# elka2_tubes.net
KiCad netlist of a schematic drawn in Altium Designer
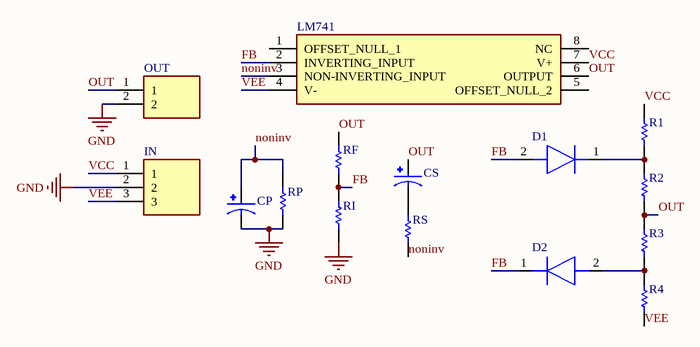
[diagram p0: elka2_tubes.SchDoc]

(export (version "E")
  (design (tool "Eeschema 10.0.6"))
  (components
    (comp (ref "CP")
      (value "elco_kecil")
      (footprint "elco_kecil")
      (description "CAP ALUM 10UF 20% 25V RADIAL")
      (fields (field (name "MF") "Panasonic") (field (name "MP") "EEA-GA1E100"))
      (libsource (lib "elco_kecil") (part "elco_kecil"))
    )
    (comp (ref "CS")
      (value "elco_kecil")
      (footprint "elco_kecil")
      (description "CAP ALUM 10UF 20% 25V RADIAL")
      (fields (field (name "MF") "Panasonic") (field (name "MP") "EEA-GA1E100"))
      (libsource (lib "elco_kecil") (part "elco_kecil"))
    )
    (comp (ref "D1")
      (value "1N4007-E3_73")
      (footprint "SamacSys:DIOAD1405W86L465D235")
      (description "Diode")
      (fields
        (field (name "MANUFACTURER_PART_NUMBER") "1N4007-E3/73")
        (field (name "MOUSER PART NUMBER") "625-1N4007-E3/73")
      )
      (libsource (lib "*") (part "1N4007-E3_73"))
    )
    (comp (ref "D2")
      (value "1N4007-E3_73")
      (footprint "SamacSys:DIOAD1405W86L465D235")
      (description "Diode")
      (fields
        (field (name "MANUFACTURER_PART_NUMBER") "1N4007-E3/73")
        (field (name "MOUSER PART NUMBER") "625-1N4007-E3/73")
      )
      (libsource (lib "*") (part "1N4007-E3_73"))
    )
    (comp (ref "IN")
      (value "KF301-3P")
      (footprint "SamacSys:KF3013P")
      (description "Connector")
      (libsource (lib "SamacSys") (part "KF301-3P"))
    )
    (comp (ref "LM741")
      (value "LM741CN_NOPB-936607701")
      (footprint "SamacSys:DIP794W53P254L959H508Q8N")
      (description "Integrated Circuit")
      (fields (field (name "MANUFACTURER_PART_NUMBER") "LM741CN/NOPB-936607701"))
      (libsource (lib "*") (part "LM741CN_NOPB-936607701"))
    )
    (comp (ref "OUT")
      (value "KF301-2P")
      (footprint "SamacSys:KF3012P")
      (description "Connector")
      (libsource (lib "SamacSys") (part "KF301-2P"))
    )
    (comp (ref "R1")
      (value "Resistor 0.25W")
      (footprint "Resistor 0.25W")
      (libsource (lib "GAPlib_DEVICES") (part "Resistor 0.25W"))
    )
    (comp (ref "R2")
      (value "Resistor 0.25W")
      (footprint "Resistor 0.25W")
      (libsource (lib "GAPlib_DEVICES") (part "Resistor 0.25W"))
    )
    (comp (ref "R3")
      (value "Resistor 0.25W")
      (footprint "Resistor 0.25W")
      (libsource (lib "GAPlib_DEVICES") (part "Resistor 0.25W"))
    )
    (comp (ref "R4")
      (value "Resistor 0.25W")
      (footprint "Resistor 0.25W")
      (libsource (lib "GAPlib_DEVICES") (part "Resistor 0.25W"))
    )
    (comp (ref "RF")
      (value "Resistor 0.25W")
      (footprint "Resistor 0.25W")
      (libsource (lib "GAPlib_DEVICES") (part "Resistor 0.25W"))
    )
    (comp (ref "RI")
      (value "Resistor 0.25W")
      (footprint "Resistor 0.25W")
      (libsource (lib "GAPlib_DEVICES") (part "Resistor 0.25W"))
    )
    (comp (ref "RP")
      (value "Resistor 0.25W")
      (footprint "Resistor 0.25W")
      (libsource (lib "GAPlib_DEVICES") (part "Resistor 0.25W"))
    )
    (comp (ref "RS")
      (value "Resistor 0.25W")
      (footprint "Resistor 0.25W")
      (libsource (lib "GAPlib_DEVICES") (part "Resistor 0.25W"))
    )
  )
  (nets
    (net (code "1") (name "/FB") (class "Default")
      (node (ref "D1") (pin "2") (pinfunction "A_2") (pintype "passive"))
      (node (ref "D2") (pin "1") (pinfunction "K_1") (pintype "passive"))
      (node (ref "LM741") (pin "2") (pinfunction "INVERTING_INPUT_2") (pintype "passive"))
      (node (ref "RF") (pin "1") (pinfunction "1_1") (pintype "passive"))
      (node (ref "RI") (pin "2") (pinfunction "2_2") (pintype "passive"))
    )
    (net (code "2") (name "/OUT") (class "Default")
      (node (ref "CS") (pin "P") (pinfunction "P_P") (pintype "passive"))
      (node (ref "LM741") (pin "6") (pinfunction "OUTPUT_6") (pintype "passive"))
      (node (ref "OUT") (pin "1") (pinfunction "1_1") (pintype "passive"))
      (node (ref "R2") (pin "1") (pinfunction "1_1") (pintype "passive"))
      (node (ref "R3") (pin "2") (pinfunction "2_2") (pintype "passive"))
      (node (ref "RF") (pin "2") (pinfunction "2_2") (pintype "passive"))
    )
    (net (code "3") (name "/VCC") (class "Default")
      (node (ref "IN") (pin "1") (pinfunction "1_1") (pintype "passive"))
      (node (ref "LM741") (pin "7") (pinfunction "V+_7") (pintype "passive"))
      (node (ref "R1") (pin "2") (pinfunction "2_2") (pintype "passive"))
    )
    (net (code "4") (name "/VEE") (class "Default")
      (node (ref "IN") (pin "3") (pinfunction "3_3") (pintype "passive"))
      (node (ref "LM741") (pin "4") (pinfunction "V-_4") (pintype "passive"))
      (node (ref "R4") (pin "1") (pinfunction "1_1") (pintype "passive"))
    )
    (net (code "5") (name "/noninv") (class "Default")
      (node (ref "CP") (pin "P") (pinfunction "P_P") (pintype "passive"))
      (node (ref "LM741") (pin "3") (pinfunction "NON-INVERTING_INPUT_3") (pintype "passive"))
      (node (ref "RP") (pin "2") (pinfunction "2_2") (pintype "passive"))
      (node (ref "RS") (pin "1") (pinfunction "1_1") (pintype "passive"))
    )
    (net (code "6") (name "GND") (class "Default")
      (node (ref "CP") (pin "N") (pinfunction "N_N") (pintype "passive"))
      (node (ref "IN") (pin "2") (pinfunction "2_2") (pintype "passive"))
      (node (ref "OUT") (pin "2") (pinfunction "2_2") (pintype "passive"))
      (node (ref "RI") (pin "1") (pinfunction "1_1") (pintype "passive"))
      (node (ref "RP") (pin "1") (pinfunction "1_1") (pintype "passive"))
    )
    (net (code "7") (name "Net-(CS-PadN)") (class "Default")
      (node (ref "CS") (pin "N") (pinfunction "N_N") (pintype "passive"))
      (node (ref "RS") (pin "2") (pinfunction "2_2") (pintype "passive"))
    )
    (net (code "8") (name "Net-(D1-K)") (class "Default")
      (node (ref "D1") (pin "1") (pinfunction "K_1") (pintype "passive"))
      (node (ref "R1") (pin "1") (pinfunction "1_1") (pintype "passive"))
      (node (ref "R2") (pin "2") (pinfunction "2_2") (pintype "passive"))
    )
    (net (code "9") (name "Net-(D2-A)") (class "Default")
      (node (ref "D2") (pin "2") (pinfunction "A_2") (pintype "passive"))
      (node (ref "R3") (pin "1") (pinfunction "1_1") (pintype "passive"))
      (node (ref "R4") (pin "2") (pinfunction "2_2") (pintype "passive"))
    )
    (net (code "10") (name "unconnected-(LM741-NC-Pad8)") (class "Default")
      (node (ref "LM741") (pin "8") (pinfunction "NC_8") (pintype "passive"))
    )
    (net (code "11") (name "unconnected-(LM741-OFFSET_NULL_1-Pad1)") (class "Default")
      (node (ref "LM741") (pin "1") (pinfunction "OFFSET_NULL_1_1") (pintype "passive"))
    )
    (net (code "12") (name "unconnected-(LM741-OFFSET_NULL_2-Pad5)") (class "Default")
      (node (ref "LM741") (pin "5") (pinfunction "OFFSET_NULL_2_5") (pintype "passive"))
    )
  )
)
